# zed_image_adapter.net
KiCad netlist of a schematic drawn in EAGLE
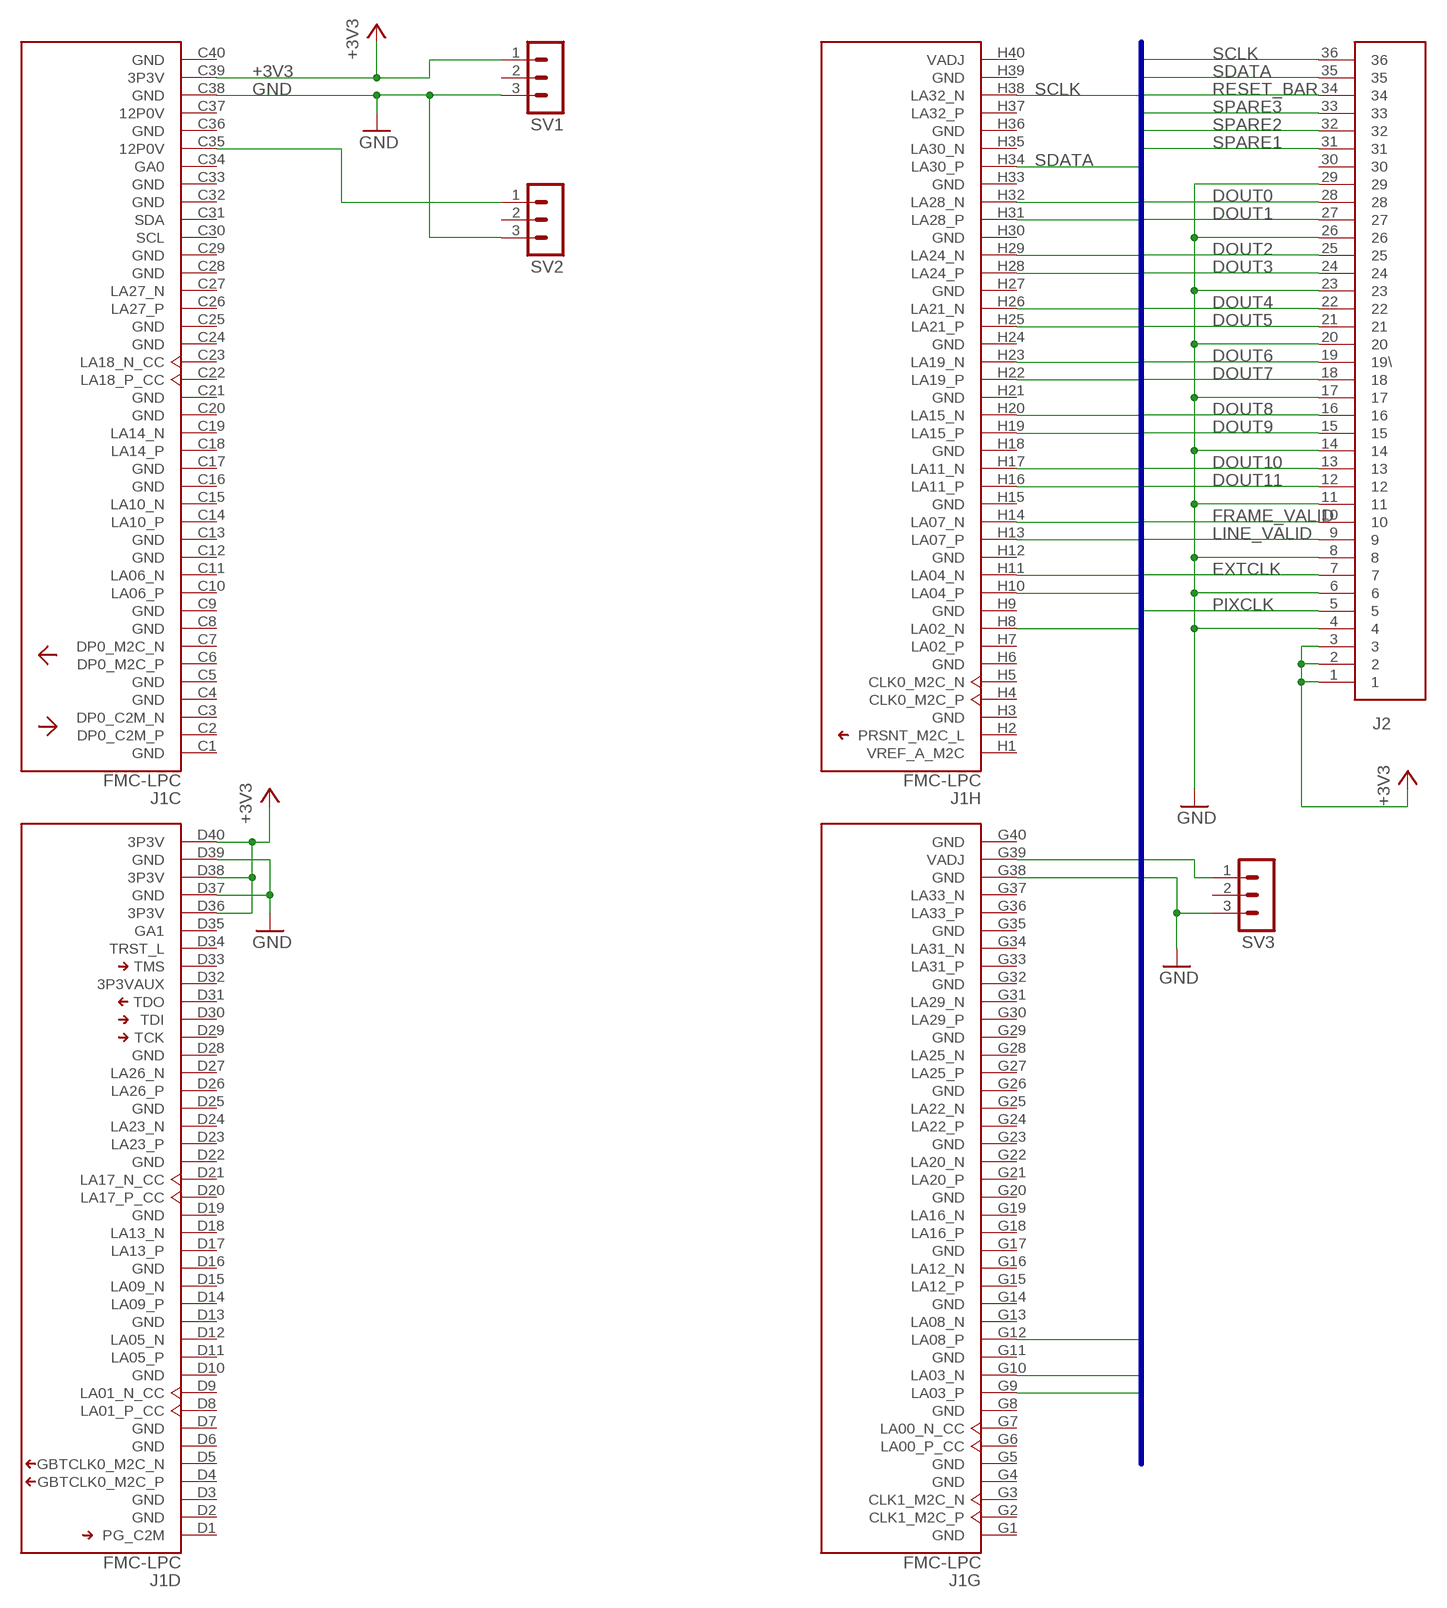
[diagram p0: schematic, sheet 1]

(export (version "E")
  (design (tool "Eeschema 10.0.6"))
  (components
    (comp (ref "J1")
      (value "FMC-LPC")
      (footprint "eagle-import:FMC-LPC-MALE")
      (fields (field (name "OC_NEWARK") "unknown"))
      (libsource (lib "eagle-import") (part "FMC-LPC"))
    )
    (comp (ref "J2")
      (value "MOLEX_54132_3662")
      (footprint "eagle-import:MOLEX_54132_3662")
      (libsource (lib "eagle-import") (part "MOLEX_54132_3662"))
    )
    (comp (ref "SV1")
      (value "MA03-1")
      (footprint "eagle-import:MA03-1")
      (libsource (lib "eagle-import") (part "MA03-1"))
    )
    (comp (ref "SV2")
      (value "MA03-1")
      (footprint "eagle-import:MA03-1")
      (libsource (lib "eagle-import") (part "MA03-1"))
    )
    (comp (ref "SV3")
      (value "MA03-1")
      (footprint "eagle-import:MA03-1")
      (libsource (lib "eagle-import") (part "MA03-1"))
    )
  )
  (nets
    (net (code "1") (name "+3V3") (class "Default")
      (node (ref "J1") (pin "C39") (pinfunction "3P3V_C39") (pintype "passive"))
      (node (ref "J1") (pin "D36") (pinfunction "3P3V_D36") (pintype "passive"))
      (node (ref "J1") (pin "D38") (pinfunction "3P3V_D38") (pintype "passive"))
      (node (ref "J1") (pin "D40") (pinfunction "3P3V_D40") (pintype "passive"))
      (node (ref "J2") (pin "1") (pinfunction "1_1") (pintype "bidirectional"))
      (node (ref "J2") (pin "2") (pinfunction "2_2") (pintype "bidirectional"))
      (node (ref "J2") (pin "3") (pinfunction "3_3") (pintype "bidirectional"))
      (node (ref "SV1") (pin "1") (pinfunction "1_1") (pintype "passive"))
    )
    (net (code "2") (name "/DOUT0") (class "Default")
      (node (ref "J1") (pin "H26") (pinfunction "LA21_N_H26") (pintype "bidirectional"))
      (node (ref "J2") (pin "28") (pinfunction "28_28") (pintype "bidirectional"))
    )
    (net (code "3") (name "/DOUT1") (class "Default")
      (node (ref "J1") (pin "H25") (pinfunction "LA21_P_H25") (pintype "bidirectional"))
      (node (ref "J2") (pin "27") (pinfunction "27_27") (pintype "bidirectional"))
    )
    (net (code "4") (name "/DOUT2") (class "Default")
      (node (ref "J1") (pin "H23") (pinfunction "LA19_N_H23") (pintype "bidirectional"))
      (node (ref "J2") (pin "25") (pinfunction "25_25") (pintype "bidirectional"))
    )
    (net (code "5") (name "/DOUT3") (class "Default")
      (node (ref "J1") (pin "H22") (pinfunction "LA19_P_H22") (pintype "bidirectional"))
      (node (ref "J2") (pin "24") (pinfunction "24_24") (pintype "bidirectional"))
    )
    (net (code "6") (name "/DOUT4") (class "Default")
      (node (ref "J1") (pin "H20") (pinfunction "LA15_N_H20") (pintype "bidirectional"))
      (node (ref "J2") (pin "22") (pinfunction "22_22") (pintype "bidirectional"))
    )
    (net (code "7") (name "/DOUT5") (class "Default")
      (node (ref "J1") (pin "H19") (pinfunction "LA15_P_H19") (pintype "bidirectional"))
      (node (ref "J2") (pin "21") (pinfunction "21_21") (pintype "bidirectional"))
    )
    (net (code "8") (name "/DOUT6") (class "Default")
      (node (ref "J1") (pin "H17") (pinfunction "LA11_N_H17") (pintype "bidirectional"))
      (node (ref "J2") (pin "19") (pinfunction "19\\_19") (pintype "bidirectional"))
    )
    (net (code "9") (name "/DOUT7") (class "Default")
      (node (ref "J1") (pin "H16") (pinfunction "LA11_P_H16") (pintype "bidirectional"))
      (node (ref "J2") (pin "18") (pinfunction "18_18") (pintype "bidirectional"))
    )
    (net (code "10") (name "/DOUT8") (class "Default")
      (node (ref "J1") (pin "H14") (pinfunction "LA07_N_H14") (pintype "bidirectional"))
      (node (ref "J2") (pin "16") (pinfunction "16_16") (pintype "bidirectional"))
    )
    (net (code "11") (name "/DOUT9") (class "Default")
      (node (ref "J1") (pin "H13") (pinfunction "LA07_P_H13") (pintype "bidirectional"))
      (node (ref "J2") (pin "15") (pinfunction "15_15") (pintype "bidirectional"))
    )
    (net (code "12") (name "/DOUT10") (class "Default")
      (node (ref "J1") (pin "H11") (pinfunction "LA04_N_H11") (pintype "bidirectional"))
      (node (ref "J2") (pin "13") (pinfunction "13_13") (pintype "bidirectional"))
    )
    (net (code "13") (name "/DOUT11") (class "Default")
      (node (ref "J1") (pin "G9") (pinfunction "LA03_P_G9") (pintype "bidirectional"))
      (node (ref "J2") (pin "12") (pinfunction "12_12") (pintype "bidirectional"))
    )
    (net (code "14") (name "/EXTCLK") (class "Default")
      (node (ref "J1") (pin "H10") (pinfunction "LA04_P_H10") (pintype "bidirectional"))
      (node (ref "J2") (pin "7") (pinfunction "7_7") (pintype "bidirectional"))
    )
    (net (code "15") (name "/FRAME_VALID") (class "Default")
      (node (ref "J1") (pin "G10") (pinfunction "LA03_N_G10") (pintype "bidirectional"))
      (node (ref "J2") (pin "10") (pinfunction "10_10") (pintype "bidirectional"))
    )
    (net (code "16") (name "/LINE_VALID") (class "Default")
      (node (ref "J1") (pin "G12") (pinfunction "LA08_P_G12") (pintype "bidirectional"))
      (node (ref "J2") (pin "9") (pinfunction "9_9") (pintype "bidirectional"))
    )
    (net (code "17") (name "/PIXCLK") (class "Default")
      (node (ref "J1") (pin "H8") (pinfunction "LA02_N_H8") (pintype "bidirectional"))
      (node (ref "J2") (pin "5") (pinfunction "5_5") (pintype "bidirectional"))
    )
    (net (code "18") (name "/RESET_BAR") (class "Default")
      (node (ref "J1") (pin "H32") (pinfunction "LA28_N_H32") (pintype "bidirectional"))
      (node (ref "J2") (pin "34") (pinfunction "34_34") (pintype "bidirectional"))
    )
    (net (code "19") (name "/SCLK") (class "Default")
      (node (ref "J1") (pin "H38") (pinfunction "LA32_N_H38") (pintype "bidirectional"))
      (node (ref "J2") (pin "36") (pinfunction "36_36") (pintype "bidirectional"))
    )
    (net (code "20") (name "/SDATA") (class "Default")
      (node (ref "J1") (pin "H34") (pinfunction "LA30_P_H34") (pintype "bidirectional"))
      (node (ref "J2") (pin "35") (pinfunction "35_35") (pintype "bidirectional"))
    )
    (net (code "21") (name "/SPARE1") (class "Default")
      (node (ref "J1") (pin "H31") (pinfunction "LA28_P_H31") (pintype "bidirectional"))
      (node (ref "J2") (pin "31") (pinfunction "31_31") (pintype "bidirectional"))
    )
    (net (code "22") (name "/SPARE2") (class "Default")
      (node (ref "J1") (pin "H29") (pinfunction "LA24_N_H29") (pintype "bidirectional"))
      (node (ref "J2") (pin "32") (pinfunction "32_32") (pintype "bidirectional"))
    )
    (net (code "23") (name "/SPARE3") (class "Default")
      (node (ref "J1") (pin "H28") (pinfunction "LA24_P_H28") (pintype "bidirectional"))
      (node (ref "J2") (pin "33") (pinfunction "33_33") (pintype "bidirectional"))
    )
    (net (code "24") (name "GND") (class "Default")
      (node (ref "J1") (pin "C38") (pinfunction "GND_C38") (pintype "passive"))
      (node (ref "J1") (pin "D37") (pinfunction "GND_D37") (pintype "passive"))
      (node (ref "J1") (pin "D39") (pinfunction "GND_D39") (pintype "passive"))
      (node (ref "J1") (pin "G38") (pinfunction "GND_G38") (pintype "passive"))
      (node (ref "J2") (pin "11") (pinfunction "11_11") (pintype "bidirectional"))
      (node (ref "J2") (pin "14") (pinfunction "14_14") (pintype "bidirectional"))
      (node (ref "J2") (pin "17") (pinfunction "17_17") (pintype "bidirectional"))
      (node (ref "J2") (pin "20") (pinfunction "20_20") (pintype "bidirectional"))
      (node (ref "J2") (pin "23") (pinfunction "23_23") (pintype "bidirectional"))
      (node (ref "J2") (pin "26") (pinfunction "26_26") (pintype "bidirectional"))
      (node (ref "J2") (pin "29") (pinfunction "29_29") (pintype "bidirectional"))
      (node (ref "J2") (pin "4") (pinfunction "4_4") (pintype "bidirectional"))
      (node (ref "J2") (pin "6") (pinfunction "6_6") (pintype "bidirectional"))
      (node (ref "J2") (pin "8") (pinfunction "8_8") (pintype "bidirectional"))
      (node (ref "SV1") (pin "3") (pinfunction "3_3") (pintype "passive"))
      (node (ref "SV2") (pin "3") (pinfunction "3_3") (pintype "passive"))
      (node (ref "SV3") (pin "3") (pinfunction "3_3") (pintype "passive"))
    )
    (net (code "25") (name "Net-(J1A-12P0V-PadC35)") (class "Default")
      (node (ref "J1") (pin "C35") (pinfunction "12P0V_C35") (pintype "passive"))
      (node (ref "SV2") (pin "1") (pinfunction "1_1") (pintype "passive"))
    )
    (net (code "26") (name "Net-(J1C-VADJ)") (class "Default")
      (node (ref "J1") (pin "G39") (pinfunction "VADJ_G39") (pintype "passive"))
      (node (ref "SV3") (pin "1") (pinfunction "1_1") (pintype "passive"))
    )
    (net (code "27") (name "unconnected-(J1A-12P0V-PadC37)") (class "Default")
      (node (ref "J1") (pin "C37") (pinfunction "12P0V_C37") (pintype "passive"))
    )
    (net (code "28") (name "unconnected-(J1A-DP0_C2M_N-PadC3)") (class "Default")
      (node (ref "J1") (pin "C3") (pinfunction "DP0_C2M_N_C3") (pintype "output"))
    )
    (net (code "29") (name "unconnected-(J1A-DP0_C2M_P-PadC2)") (class "Default")
      (node (ref "J1") (pin "C2") (pinfunction "DP0_C2M_P_C2") (pintype "output"))
    )
    (net (code "30") (name "unconnected-(J1A-DP0_M2C_N-PadC7)") (class "Default")
      (node (ref "J1") (pin "C7") (pinfunction "DP0_M2C_N_C7") (pintype "input"))
    )
    (net (code "31") (name "unconnected-(J1A-DP0_M2C_P-PadC6)") (class "Default")
      (node (ref "J1") (pin "C6") (pinfunction "DP0_M2C_P_C6") (pintype "input"))
    )
    (net (code "32") (name "unconnected-(J1A-GA0-PadC34)") (class "Default")
      (node (ref "J1") (pin "C34") (pinfunction "GA0_C34") (pintype "output"))
    )
    (net (code "33") (name "unconnected-(J1A-GND-PadC1)") (class "Default")
      (node (ref "J1") (pin "C1") (pinfunction "GND_C1") (pintype "passive"))
    )
    (net (code "34") (name "unconnected-(J1A-GND-PadC4)") (class "Default")
      (node (ref "J1") (pin "C4") (pinfunction "GND_C4") (pintype "passive"))
    )
    (net (code "35") (name "unconnected-(J1A-GND-PadC5)") (class "Default")
      (node (ref "J1") (pin "C5") (pinfunction "GND_C5") (pintype "passive"))
    )
    (net (code "36") (name "unconnected-(J1A-GND-PadC8)") (class "Default")
      (node (ref "J1") (pin "C8") (pinfunction "GND_C8") (pintype "passive"))
    )
    (net (code "37") (name "unconnected-(J1A-GND-PadC9)") (class "Default")
      (node (ref "J1") (pin "C9") (pinfunction "GND_C9") (pintype "passive"))
    )
    (net (code "38") (name "unconnected-(J1A-GND-PadC12)") (class "Default")
      (node (ref "J1") (pin "C12") (pinfunction "GND_C12") (pintype "passive"))
    )
    (net (code "39") (name "unconnected-(J1A-GND-PadC13)") (class "Default")
      (node (ref "J1") (pin "C13") (pinfunction "GND_C13") (pintype "passive"))
    )
    (net (code "40") (name "unconnected-(J1A-GND-PadC16)") (class "Default")
      (node (ref "J1") (pin "C16") (pinfunction "GND_C16") (pintype "passive"))
    )
    (net (code "41") (name "unconnected-(J1A-GND-PadC17)") (class "Default")
      (node (ref "J1") (pin "C17") (pinfunction "GND_C17") (pintype "passive"))
    )
    (net (code "42") (name "unconnected-(J1A-GND-PadC20)") (class "Default")
      (node (ref "J1") (pin "C20") (pinfunction "GND_C20") (pintype "passive"))
    )
    (net (code "43") (name "unconnected-(J1A-GND-PadC21)") (class "Default")
      (node (ref "J1") (pin "C21") (pinfunction "GND_C21") (pintype "passive"))
    )
    (net (code "44") (name "unconnected-(J1A-GND-PadC24)") (class "Default")
      (node (ref "J1") (pin "C24") (pinfunction "GND_C24") (pintype "passive"))
    )
    (net (code "45") (name "unconnected-(J1A-GND-PadC25)") (class "Default")
      (node (ref "J1") (pin "C25") (pinfunction "GND_C25") (pintype "passive"))
    )
    (net (code "46") (name "unconnected-(J1A-GND-PadC28)") (class "Default")
      (node (ref "J1") (pin "C28") (pinfunction "GND_C28") (pintype "passive"))
    )
    (net (code "47") (name "unconnected-(J1A-GND-PadC29)") (class "Default")
      (node (ref "J1") (pin "C29") (pinfunction "GND_C29") (pintype "passive"))
    )
    (net (code "48") (name "unconnected-(J1A-GND-PadC32)") (class "Default")
      (node (ref "J1") (pin "C32") (pinfunction "GND_C32") (pintype "passive"))
    )
    (net (code "49") (name "unconnected-(J1A-GND-PadC33)") (class "Default")
      (node (ref "J1") (pin "C33") (pinfunction "GND_C33") (pintype "passive"))
    )
    (net (code "50") (name "unconnected-(J1A-GND-PadC36)") (class "Default")
      (node (ref "J1") (pin "C36") (pinfunction "GND_C36") (pintype "passive"))
    )
    (net (code "51") (name "unconnected-(J1A-GND-PadC40)") (class "Default")
      (node (ref "J1") (pin "C40") (pinfunction "GND_C40") (pintype "passive"))
    )
    (net (code "52") (name "unconnected-(J1A-LA06_N-PadC11)") (class "Default")
      (node (ref "J1") (pin "C11") (pinfunction "LA06_N_C11") (pintype "bidirectional"))
    )
    (net (code "53") (name "unconnected-(J1A-LA06_P-PadC10)") (class "Default")
      (node (ref "J1") (pin "C10") (pinfunction "LA06_P_C10") (pintype "bidirectional"))
    )
    (net (code "54") (name "unconnected-(J1A-LA10_N-PadC15)") (class "Default")
      (node (ref "J1") (pin "C15") (pinfunction "LA10_N_C15") (pintype "bidirectional"))
    )
    (net (code "55") (name "unconnected-(J1A-LA10_P-PadC14)") (class "Default")
      (node (ref "J1") (pin "C14") (pinfunction "LA10_P_C14") (pintype "bidirectional"))
    )
    (net (code "56") (name "unconnected-(J1A-LA14_N-PadC19)") (class "Default")
      (node (ref "J1") (pin "C19") (pinfunction "LA14_N_C19") (pintype "bidirectional"))
    )
    (net (code "57") (name "unconnected-(J1A-LA14_P-PadC18)") (class "Default")
      (node (ref "J1") (pin "C18") (pinfunction "LA14_P_C18") (pintype "bidirectional"))
    )
    (net (code "58") (name "unconnected-(J1A-LA18_N_CC-PadC23)") (class "Default")
      (node (ref "J1") (pin "C23") (pinfunction "LA18_N_CC_C23") (pintype "bidirectional"))
    )
    (net (code "59") (name "unconnected-(J1A-LA18_P_CC-PadC22)") (class "Default")
      (node (ref "J1") (pin "C22") (pinfunction "LA18_P_CC_C22") (pintype "bidirectional"))
    )
    (net (code "60") (name "unconnected-(J1A-LA27_N-PadC27)") (class "Default")
      (node (ref "J1") (pin "C27") (pinfunction "LA27_N_C27") (pintype "bidirectional"))
    )
    (net (code "61") (name "unconnected-(J1A-LA27_P-PadC26)") (class "Default")
      (node (ref "J1") (pin "C26") (pinfunction "LA27_P_C26") (pintype "bidirectional"))
    )
    (net (code "62") (name "unconnected-(J1A-SCL-PadC30)") (class "Default")
      (node (ref "J1") (pin "C30") (pinfunction "SCL_C30") (pintype "bidirectional"))
    )
    (net (code "63") (name "unconnected-(J1A-SDA-PadC31)") (class "Default")
      (node (ref "J1") (pin "C31") (pinfunction "SDA_C31") (pintype "bidirectional"))
    )
    (net (code "64") (name "unconnected-(J1B-3P3VAUX-PadD32)") (class "Default")
      (node (ref "J1") (pin "D32") (pinfunction "3P3VAUX_D32") (pintype "passive"))
    )
    (net (code "65") (name "unconnected-(J1B-GA1-PadD35)") (class "Default")
      (node (ref "J1") (pin "D35") (pinfunction "GA1_D35") (pintype "output"))
    )
    (net (code "66") (name "unconnected-(J1B-GBTCLK0_M2C_N-PadD5)") (class "Default")
      (node (ref "J1") (pin "D5") (pinfunction "GBTCLK0_M2C_N_D5") (pintype "input"))
    )
    (net (code "67") (name "unconnected-(J1B-GBTCLK0_M2C_P-PadD4)") (class "Default")
      (node (ref "J1") (pin "D4") (pinfunction "GBTCLK0_M2C_P_D4") (pintype "input"))
    )
    (net (code "68") (name "unconnected-(J1B-GND-PadD2)") (class "Default")
      (node (ref "J1") (pin "D2") (pinfunction "GND_D2") (pintype "passive"))
    )
    (net (code "69") (name "unconnected-(J1B-GND-PadD3)") (class "Default")
      (node (ref "J1") (pin "D3") (pinfunction "GND_D3") (pintype "passive"))
    )
    (net (code "70") (name "unconnected-(J1B-GND-PadD6)") (class "Default")
      (node (ref "J1") (pin "D6") (pinfunction "GND_D6") (pintype "passive"))
    )
    (net (code "71") (name "unconnected-(J1B-GND-PadD7)") (class "Default")
      (node (ref "J1") (pin "D7") (pinfunction "GND_D7") (pintype "passive"))
    )
    (net (code "72") (name "unconnected-(J1B-GND-PadD10)") (class "Default")
      (node (ref "J1") (pin "D10") (pinfunction "GND_D10") (pintype "passive"))
    )
    (net (code "73") (name "unconnected-(J1B-GND-PadD13)") (class "Default")
      (node (ref "J1") (pin "D13") (pinfunction "GND_D13") (pintype "passive"))
    )
    (net (code "74") (name "unconnected-(J1B-GND-PadD16)") (class "Default")
      (node (ref "J1") (pin "D16") (pinfunction "GND_D16") (pintype "passive"))
    )
    (net (code "75") (name "unconnected-(J1B-GND-PadD19)") (class "Default")
      (node (ref "J1") (pin "D19") (pinfunction "GND_D19") (pintype "passive"))
    )
    (net (code "76") (name "unconnected-(J1B-GND-PadD22)") (class "Default")
      (node (ref "J1") (pin "D22") (pinfunction "GND_D22") (pintype "passive"))
    )
    (net (code "77") (name "unconnected-(J1B-GND-PadD25)") (class "Default")
      (node (ref "J1") (pin "D25") (pinfunction "GND_D25") (pintype "passive"))
    )
    (net (code "78") (name "unconnected-(J1B-GND-PadD28)") (class "Default")
      (node (ref "J1") (pin "D28") (pinfunction "GND_D28") (pintype "passive"))
    )
    (net (code "79") (name "unconnected-(J1B-LA01_N_CC-PadD9)") (class "Default")
      (node (ref "J1") (pin "D9") (pinfunction "LA01_N_CC_D9") (pintype "bidirectional"))
    )
    (net (code "80") (name "unconnected-(J1B-LA01_P_CC-PadD8)") (class "Default")
      (node (ref "J1") (pin "D8") (pinfunction "LA01_P_CC_D8") (pintype "bidirectional"))
    )
    (net (code "81") (name "unconnected-(J1B-LA05_N-PadD12)") (class "Default")
      (node (ref "J1") (pin "D12") (pinfunction "LA05_N_D12") (pintype "bidirectional"))
    )
    (net (code "82") (name "unconnected-(J1B-LA05_P-PadD11)") (class "Default")
      (node (ref "J1") (pin "D11") (pinfunction "LA05_P_D11") (pintype "bidirectional"))
    )
    (net (code "83") (name "unconnected-(J1B-LA09_N-PadD15)") (class "Default")
      (node (ref "J1") (pin "D15") (pinfunction "LA09_N_D15") (pintype "bidirectional"))
    )
    (net (code "84") (name "unconnected-(J1B-LA09_P-PadD14)") (class "Default")
      (node (ref "J1") (pin "D14") (pinfunction "LA09_P_D14") (pintype "bidirectional"))
    )
    (net (code "85") (name "unconnected-(J1B-LA13_N-PadD18)") (class "Default")
      (node (ref "J1") (pin "D18") (pinfunction "LA13_N_D18") (pintype "bidirectional"))
    )
    (net (code "86") (name "unconnected-(J1B-LA13_P-PadD17)") (class "Default")
      (node (ref "J1") (pin "D17") (pinfunction "LA13_P_D17") (pintype "bidirectional"))
    )
    (net (code "87") (name "unconnected-(J1B-LA17_N_CC-PadD21)") (class "Default")
      (node (ref "J1") (pin "D21") (pinfunction "LA17_N_CC_D21") (pintype "bidirectional"))
    )
    (net (code "88") (name "unconnected-(J1B-LA17_P_CC-PadD20)") (class "Default")
      (node (ref "J1") (pin "D20") (pinfunction "LA17_P_CC_D20") (pintype "bidirectional"))
    )
    (net (code "89") (name "unconnected-(J1B-LA23_N-PadD24)") (class "Default")
      (node (ref "J1") (pin "D24") (pinfunction "LA23_N_D24") (pintype "bidirectional"))
    )
    (net (code "90") (name "unconnected-(J1B-LA23_P-PadD23)") (class "Default")
      (node (ref "J1") (pin "D23") (pinfunction "LA23_P_D23") (pintype "bidirectional"))
    )
    (net (code "91") (name "unconnected-(J1B-LA26_N-PadD27)") (class "Default")
      (node (ref "J1") (pin "D27") (pinfunction "LA26_N_D27") (pintype "bidirectional"))
    )
    (net (code "92") (name "unconnected-(J1B-LA26_P-PadD26)") (class "Default")
      (node (ref "J1") (pin "D26") (pinfunction "LA26_P_D26") (pintype "bidirectional"))
    )
    (net (code "93") (name "unconnected-(J1B-PG_C2M-PadD1)") (class "Default")
      (node (ref "J1") (pin "D1") (pinfunction "PG_C2M_D1") (pintype "output"))
    )
    (net (code "94") (name "unconnected-(J1B-TCK-PadD29)") (class "Default")
      (node (ref "J1") (pin "D29") (pinfunction "TCK_D29") (pintype "output"))
    )
    (net (code "95") (name "unconnected-(J1B-TDI-PadD30)") (class "Default")
      (node (ref "J1") (pin "D30") (pinfunction "TDI_D30") (pintype "output"))
    )
    (net (code "96") (name "unconnected-(J1B-TDO-PadD31)") (class "Default")
      (node (ref "J1") (pin "D31") (pinfunction "TDO_D31") (pintype "input"))
    )
    (net (code "97") (name "unconnected-(J1B-TMS-PadD33)") (class "Default")
      (node (ref "J1") (pin "D33") (pinfunction "TMS_D33") (pintype "output"))
    )
    (net (code "98") (name "unconnected-(J1B-TRST_L-PadD34)") (class "Default")
      (node (ref "J1") (pin "D34") (pinfunction "TRST_L_D34") (pintype "output"))
    )
    (net (code "99") (name "unconnected-(J1C-CLK1_M2C_N-PadG3)") (class "Default")
      (node (ref "J1") (pin "G3") (pinfunction "CLK1_M2C_N_G3") (pintype "bidirectional"))
    )
    (net (code "100") (name "unconnected-(J1C-CLK1_M2C_P-PadG2)") (class "Default")
      (node (ref "J1") (pin "G2") (pinfunction "CLK1_M2C_P_G2") (pintype "bidirectional"))
    )
    (net (code "101") (name "unconnected-(J1C-GND-PadG1)") (class "Default")
      (node (ref "J1") (pin "G1") (pinfunction "GND_G1") (pintype "passive"))
    )
    (net (code "102") (name "unconnected-(J1C-GND-PadG4)") (class "Default")
      (node (ref "J1") (pin "G4") (pinfunction "GND_G4") (pintype "passive"))
    )
    (net (code "103") (name "unconnected-(J1C-GND-PadG5)") (class "Default")
      (node (ref "J1") (pin "G5") (pinfunction "GND_G5") (pintype "passive"))
    )
    (net (code "104") (name "unconnected-(J1C-GND-PadG8)") (class "Default")
      (node (ref "J1") (pin "G8") (pinfunction "GND_G8") (pintype "passive"))
    )
    (net (code "105") (name "unconnected-(J1C-GND-PadG11)") (class "Default")
      (node (ref "J1") (pin "G11") (pinfunction "GND_G11") (pintype "passive"))
    )
    (net (code "106") (name "unconnected-(J1C-GND-PadG14)") (class "Default")
      (node (ref "J1") (pin "G14") (pinfunction "GND_G14") (pintype "passive"))
    )
    (net (code "107") (name "unconnected-(J1C-GND-PadG17)") (class "Default")
      (node (ref "J1") (pin "G17") (pinfunction "GND_G17") (pintype "passive"))
    )
    (net (code "108") (name "unconnected-(J1C-GND-PadG20)") (class "Default")
      (node (ref "J1") (pin "G20") (pinfunction "GND_G20") (pintype "passive"))
    )
    (net (code "109") (name "unconnected-(J1C-GND-PadG23)") (class "Default")
      (node (ref "J1") (pin "G23") (pinfunction "GND_G23") (pintype "passive"))
    )
    (net (code "110") (name "unconnected-(J1C-GND-PadG26)") (class "Default")
      (node (ref "J1") (pin "G26") (pinfunction "GND_G26") (pintype "passive"))
    )
    (net (code "111") (name "unconnected-(J1C-GND-PadG29)") (class "Default")
      (node (ref "J1") (pin "G29") (pinfunction "GND_G29") (pintype "passive"))
    )
    (net (code "112") (name "unconnected-(J1C-GND-PadG32)") (class "Default")
      (node (ref "J1") (pin "G32") (pinfunction "GND_G32") (pintype "passive"))
    )
    (net (code "113") (name "unconnected-(J1C-GND-PadG35)") (class "Default")
      (node (ref "J1") (pin "G35") (pinfunction "GND_G35") (pintype "passive"))
    )
    (net (code "114") (name "unconnected-(J1C-GND-PadG40)") (class "Default")
      (node (ref "J1") (pin "G40") (pinfunction "GND_G40") (pintype "passive"))
    )
    (net (code "115") (name "unconnected-(J1C-LA00_N_CC-PadG7)") (class "Default")
      (node (ref "J1") (pin "G7") (pinfunction "LA00_N_CC_G7") (pintype "bidirectional"))
    )
    (net (code "116") (name "unconnected-(J1C-LA00_P_CC-PadG6)") (class "Default")
      (node (ref "J1") (pin "G6") (pinfunction "LA00_P_CC_G6") (pintype "bidirectional"))
    )
    (net (code "117") (name "unconnected-(J1C-LA08_N-PadG13)") (class "Default")
      (node (ref "J1") (pin "G13") (pinfunction "LA08_N_G13") (pintype "bidirectional"))
    )
    (net (code "118") (name "unconnected-(J1C-LA12_N-PadG16)") (class "Default")
      (node (ref "J1") (pin "G16") (pinfunction "LA12_N_G16") (pintype "bidirectional"))
    )
    (net (code "119") (name "unconnected-(J1C-LA12_P-PadG15)") (class "Default")
      (node (ref "J1") (pin "G15") (pinfunction "LA12_P_G15") (pintype "bidirectional"))
    )
    (net (code "120") (name "unconnected-(J1C-LA16_N-PadG19)") (class "Default")
      (node (ref "J1") (pin "G19") (pinfunction "LA16_N_G19") (pintype "bidirectional"))
    )
    (net (code "121") (name "unconnected-(J1C-LA16_P-PadG18)") (class "Default")
      (node (ref "J1") (pin "G18") (pinfunction "LA16_P_G18") (pintype "bidirectional"))
    )
    (net (code "122") (name "unconnected-(J1C-LA20_N-PadG22)") (class "Default")
      (node (ref "J1") (pin "G22") (pinfunction "LA20_N_G22") (pintype "bidirectional"))
    )
    (net (code "123") (name "unconnected-(J1C-LA20_P-PadG21)") (class "Default")
      (node (ref "J1") (pin "G21") (pinfunction "LA20_P_G21") (pintype "bidirectional"))
    )
    (net (code "124") (name "unconnected-(J1C-LA22_N-PadG25)") (class "Default")
      (node (ref "J1") (pin "G25") (pinfunction "LA22_N_G25") (pintype "bidirectional"))
    )
    (net (code "125") (name "unconnected-(J1C-LA22_P-PadG24)") (class "Default")
      (node (ref "J1") (pin "G24") (pinfunction "LA22_P_G24") (pintype "bidirectional"))
    )
    (net (code "126") (name "unconnected-(J1C-LA25_N-PadG28)") (class "Default")
      (node (ref "J1") (pin "G28") (pinfunction "LA25_N_G28") (pintype "bidirectional"))
    )
    (net (code "127") (name "unconnected-(J1C-LA25_P-PadG27)") (class "Default")
      (node (ref "J1") (pin "G27") (pinfunction "LA25_P_G27") (pintype "bidirectional"))
    )
    (net (code "128") (name "unconnected-(J1C-LA29_N-PadG31)") (class "Default")
      (node (ref "J1") (pin "G31") (pinfunction "LA29_N_G31") (pintype "bidirectional"))
    )
    (net (code "129") (name "unconnected-(J1C-LA29_P-PadG30)") (class "Default")
      (node (ref "J1") (pin "G30") (pinfunction "LA29_P_G30") (pintype "bidirectional"))
    )
    (net (code "130") (name "unconnected-(J1C-LA31_N-PadG34)") (class "Default")
      (node (ref "J1") (pin "G34") (pinfunction "LA31_N_G34") (pintype "bidirectional"))
    )
    (net (code "131") (name "unconnected-(J1C-LA31_P-PadG33)") (class "Default")
      (node (ref "J1") (pin "G33") (pinfunction "LA31_P_G33") (pintype "bidirectional"))
    )
    (net (code "132") (name "unconnected-(J1C-LA33_N-PadG37)") (class "Default")
      (node (ref "J1") (pin "G37") (pinfunction "LA33_N_G37") (pintype "bidirectional"))
    )
    (net (code "133") (name "unconnected-(J1C-LA33_P-PadG36)") (class "Default")
      (node (ref "J1") (pin "G36") (pinfunction "LA33_P_G36") (pintype "bidirectional"))
    )
    (net (code "134") (name "unconnected-(J1D-CLK0_M2C_N-PadH5)") (class "Default")
      (node (ref "J1") (pin "H5") (pinfunction "CLK0_M2C_N_H5") (pintype "bidirectional"))
    )
    (net (code "135") (name "unconnected-(J1D-CLK0_M2C_P-PadH4)") (class "Default")
      (node (ref "J1") (pin "H4") (pinfunction "CLK0_M2C_P_H4") (pintype "bidirectional"))
    )
    (net (code "136") (name "unconnected-(J1D-GND-PadH3)") (class "Default")
      (node (ref "J1") (pin "H3") (pinfunction "GND_H3") (pintype "passive"))
    )
    (net (code "137") (name "unconnected-(J1D-GND-PadH6)") (class "Default")
      (node (ref "J1") (pin "H6") (pinfunction "GND_H6") (pintype "passive"))
    )
    (net (code "138") (name "unconnected-(J1D-GND-PadH9)") (class "Default")
      (node (ref "J1") (pin "H9") (pinfunction "GND_H9") (pintype "passive"))
    )
    (net (code "139") (name "unconnected-(J1D-GND-PadH12)") (class "Default")
      (node (ref "J1") (pin "H12") (pinfunction "GND_H12") (pintype "passive"))
    )
    (net (code "140") (name "unconnected-(J1D-GND-PadH15)") (class "Default")
      (node (ref "J1") (pin "H15") (pinfunction "GND_H15") (pintype "passive"))
    )
    (net (code "141") (name "unconnected-(J1D-GND-PadH18)") (class "Default")
      (node (ref "J1") (pin "H18") (pinfunction "GND_H18") (pintype "passive"))
    )
    (net (code "142") (name "unconnected-(J1D-GND-PadH21)") (class "Default")
      (node (ref "J1") (pin "H21") (pinfunction "GND_H21") (pintype "passive"))
    )
    (net (code "143") (name "unconnected-(J1D-GND-PadH24)") (class "Default")
      (node (ref "J1") (pin "H24") (pinfunction "GND_H24") (pintype "passive"))
    )
    (net (code "144") (name "unconnected-(J1D-GND-PadH27)") (class "Default")
      (node (ref "J1") (pin "H27") (pinfunction "GND_H27") (pintype "passive"))
    )
    (net (code "145") (name "unconnected-(J1D-GND-PadH30)") (class "Default")
      (node (ref "J1") (pin "H30") (pinfunction "GND_H30") (pintype "passive"))
    )
    (net (code "146") (name "unconnected-(J1D-GND-PadH33)") (class "Default")
      (node (ref "J1") (pin "H33") (pinfunction "GND_H33") (pintype "passive"))
    )
    (net (code "147") (name "unconnected-(J1D-GND-PadH36)") (class "Default")
      (node (ref "J1") (pin "H36") (pinfunction "GND_H36") (pintype "passive"))
    )
    (net (code "148") (name "unconnected-(J1D-GND-PadH39)") (class "Default")
      (node (ref "J1") (pin "H39") (pinfunction "GND_H39") (pintype "passive"))
    )
    (net (code "149") (name "unconnected-(J1D-LA02_P-PadH7)") (class "Default")
      (node (ref "J1") (pin "H7") (pinfunction "LA02_P_H7") (pintype "bidirectional"))
    )
    (net (code "150") (name "unconnected-(J1D-LA30_N-PadH35)") (class "Default")
      (node (ref "J1") (pin "H35") (pinfunction "LA30_N_H35") (pintype "bidirectional"))
    )
    (net (code "151") (name "unconnected-(J1D-LA32_P-PadH37)") (class "Default")
      (node (ref "J1") (pin "H37") (pinfunction "LA32_P_H37") (pintype "bidirectional"))
    )
    (net (code "152") (name "unconnected-(J1D-PRSNT_M2C_L-PadH2)") (class "Default")
      (node (ref "J1") (pin "H2") (pinfunction "PRSNT_M2C_L_H2") (pintype "input"))
    )
    (net (code "153") (name "unconnected-(J1D-VADJ-PadH40)") (class "Default")
      (node (ref "J1") (pin "H40") (pinfunction "VADJ_H40") (pintype "passive"))
    )
    (net (code "154") (name "unconnected-(J1D-VREF_A_M2C-PadH1)") (class "Default")
      (node (ref "J1") (pin "H1") (pinfunction "VREF_A_M2C_H1") (pintype "passive"))
    )
    (net (code "155") (name "unconnected-(J2-Pad30)") (class "Default")
      (node (ref "J2") (pin "30") (pinfunction "30_30") (pintype "bidirectional"))
    )
    (net (code "156") (name "unconnected-(SV1-Pad2)") (class "Default")
      (node (ref "SV1") (pin "2") (pinfunction "2_2") (pintype "passive"))
    )
    (net (code "157") (name "unconnected-(SV2-Pad2)") (class "Default")
      (node (ref "SV2") (pin "2") (pinfunction "2_2") (pintype "passive"))
    )
    (net (code "158") (name "unconnected-(SV3-Pad2)") (class "Default")
      (node (ref "SV3") (pin "2") (pinfunction "2_2") (pintype "passive"))
    )
  )
)
